# MainControllerPower.net
KiCad netlist of a schematic drawn in Altium Designer
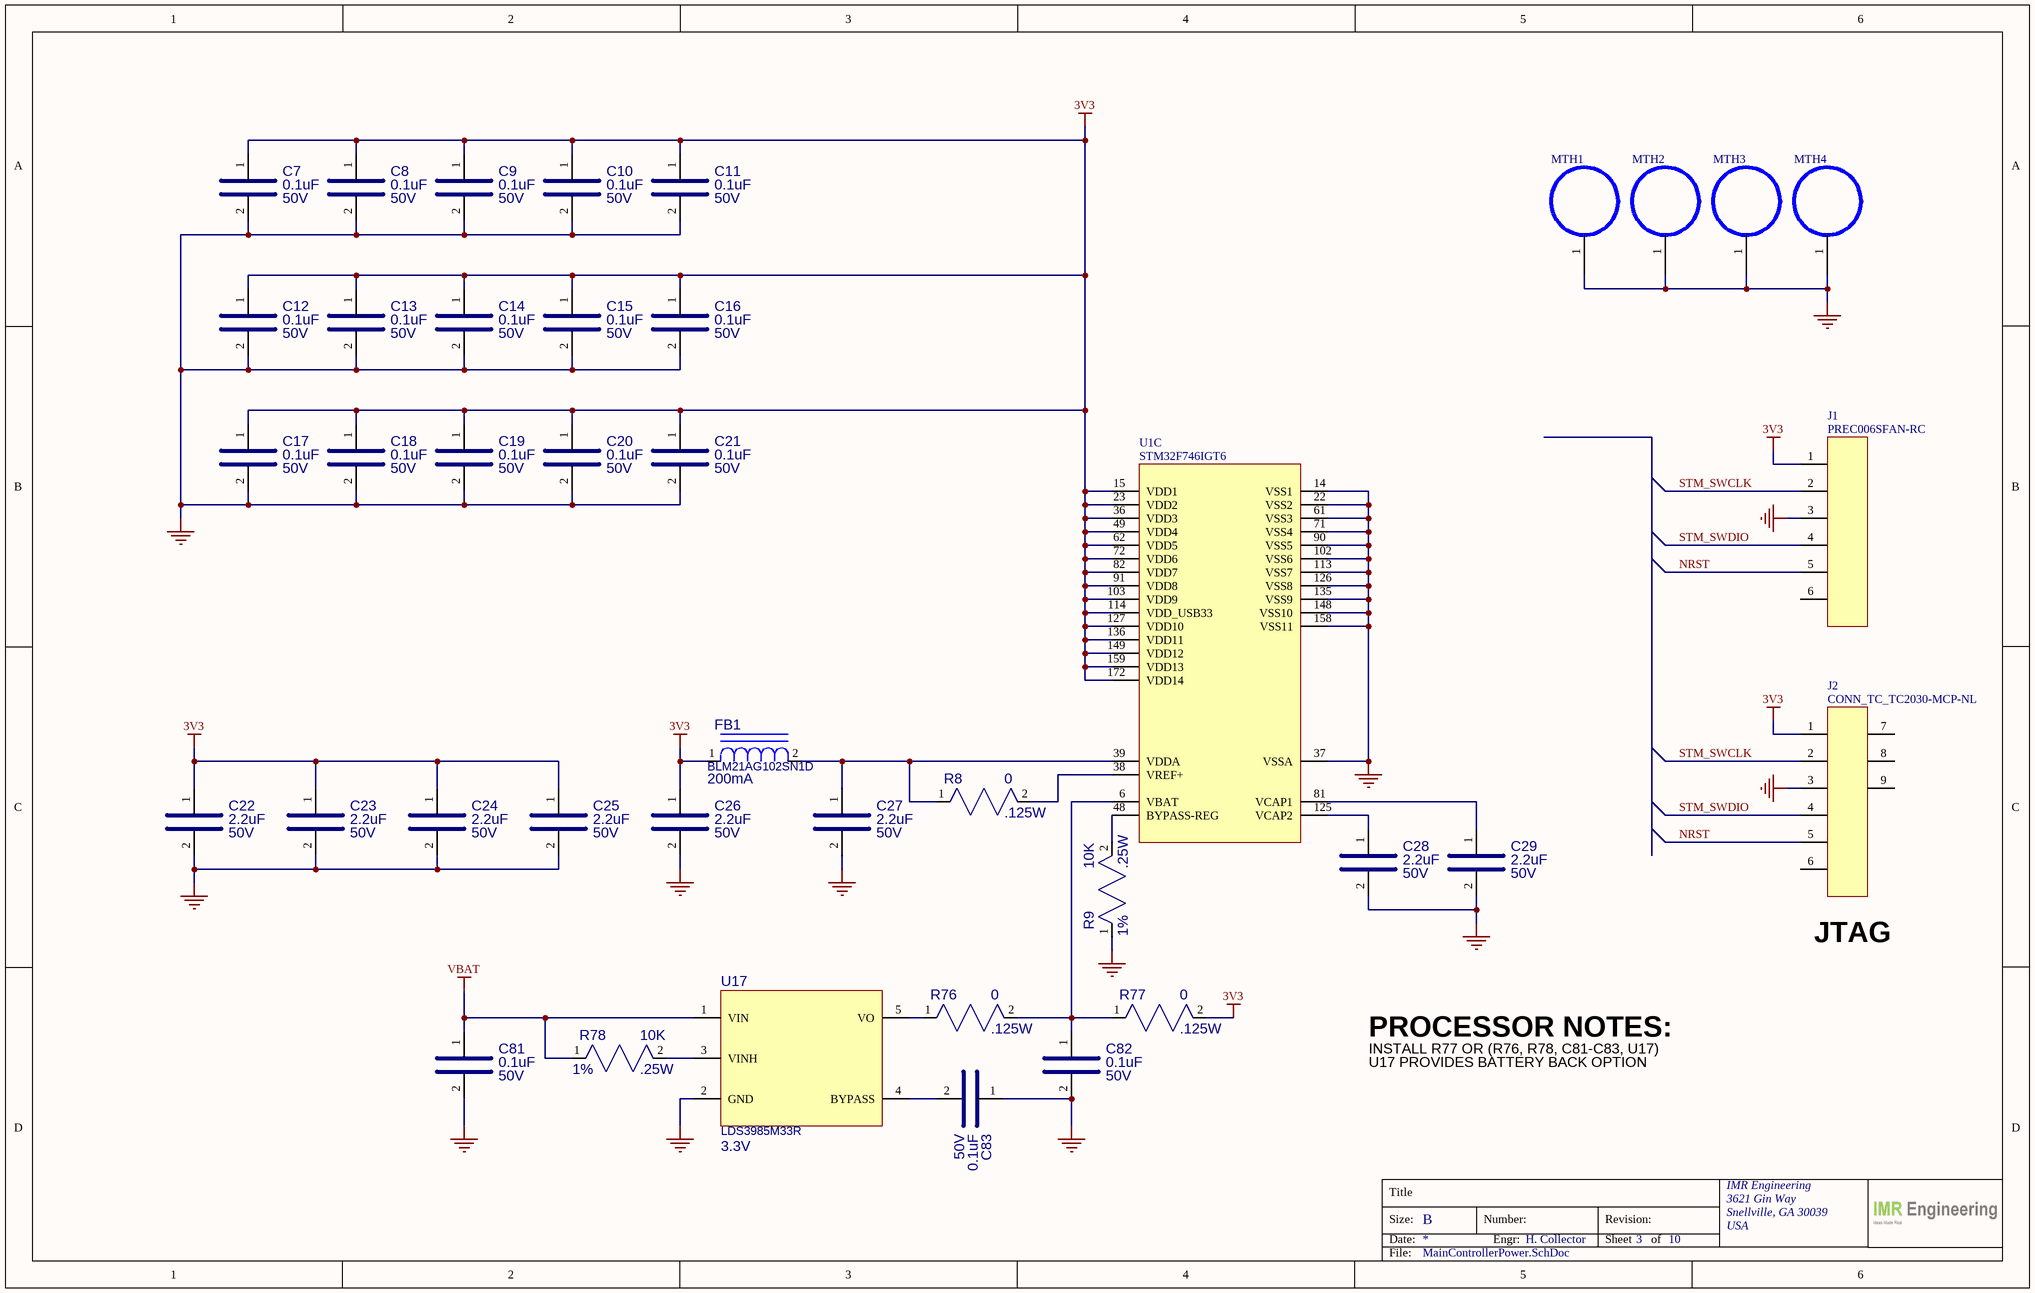
[diagram p0: MainControllerPower.SchDoc]

(export (version "E")
  (design (tool "Eeschema 10.0.6"))
  (components
    (comp (ref "C7")
      (value "0.1uF")
      (footprint "CAP_0603")
      (description "CAP CER 0.1UF 50V X7R 0603")
      (fields (field (name "MFG") "Yageo") (field (name "TOLERANCE") "10%") (field (name "VOLTAGE") "50V"))
      (libsource (lib "IMR_Lib") (part "CAP_0.1UF_50V_0603"))
    )
    (comp (ref "C8")
      (value "0.1uF")
      (footprint "CAP_0603")
      (description "CAP CER 0.1UF 50V X7R 0603")
      (fields (field (name "MFG") "Yageo") (field (name "TOLERANCE") "10%") (field (name "VOLTAGE") "50V"))
      (libsource (lib "IMR_Lib") (part "CAP_0.1UF_50V_0603"))
    )
    (comp (ref "C9")
      (value "0.1uF")
      (footprint "CAP_0603")
      (description "CAP CER 0.1UF 50V X7R 0603")
      (fields (field (name "MFG") "Yageo") (field (name "TOLERANCE") "10%") (field (name "VOLTAGE") "50V"))
      (libsource (lib "IMR_Lib") (part "CAP_0.1UF_50V_0603"))
    )
    (comp (ref "C10")
      (value "0.1uF")
      (footprint "CAP_0603")
      (description "CAP CER 0.1UF 50V X7R 0603")
      (fields (field (name "MFG") "Yageo") (field (name "TOLERANCE") "10%") (field (name "VOLTAGE") "50V"))
      (libsource (lib "IMR_Lib") (part "CAP_0.1UF_50V_0603"))
    )
    (comp (ref "C11")
      (value "0.1uF")
      (footprint "CAP_0603")
      (description "CAP CER 0.1UF 50V X7R 0603")
      (fields (field (name "MFG") "Yageo") (field (name "TOLERANCE") "10%") (field (name "VOLTAGE") "50V"))
      (libsource (lib "IMR_Lib") (part "CAP_0.1UF_50V_0603"))
    )
    (comp (ref "C12")
      (value "0.1uF")
      (footprint "CAP_0603")
      (description "CAP CER 0.1UF 50V X7R 0603")
      (fields (field (name "MFG") "Yageo") (field (name "TOLERANCE") "10%") (field (name "VOLTAGE") "50V"))
      (libsource (lib "IMR_Lib") (part "CAP_0.1UF_50V_0603"))
    )
    (comp (ref "C13")
      (value "0.1uF")
      (footprint "CAP_0603")
      (description "CAP CER 0.1UF 50V X7R 0603")
      (fields (field (name "MFG") "Yageo") (field (name "TOLERANCE") "10%") (field (name "VOLTAGE") "50V"))
      (libsource (lib "IMR_Lib") (part "CAP_0.1UF_50V_0603"))
    )
    (comp (ref "C14")
      (value "0.1uF")
      (footprint "CAP_0603")
      (description "CAP CER 0.1UF 50V X7R 0603")
      (fields (field (name "MFG") "Yageo") (field (name "TOLERANCE") "10%") (field (name "VOLTAGE") "50V"))
      (libsource (lib "IMR_Lib") (part "CAP_0.1UF_50V_0603"))
    )
    (comp (ref "C15")
      (value "0.1uF")
      (footprint "CAP_0603")
      (description "CAP CER 0.1UF 50V X7R 0603")
      (fields (field (name "MFG") "Yageo") (field (name "TOLERANCE") "10%") (field (name "VOLTAGE") "50V"))
      (libsource (lib "IMR_Lib") (part "CAP_0.1UF_50V_0603"))
    )
    (comp (ref "C16")
      (value "0.1uF")
      (footprint "CAP_0603")
      (description "CAP CER 0.1UF 50V X7R 0603")
      (fields (field (name "MFG") "Yageo") (field (name "TOLERANCE") "10%") (field (name "VOLTAGE") "50V"))
      (libsource (lib "IMR_Lib") (part "CAP_0.1UF_50V_0603"))
    )
    (comp (ref "C17")
      (value "0.1uF")
      (footprint "CAP_0603")
      (description "CAP CER 0.1UF 50V X7R 0603")
      (fields (field (name "MFG") "Yageo") (field (name "TOLERANCE") "10%") (field (name "VOLTAGE") "50V"))
      (libsource (lib "IMR_Lib") (part "CAP_0.1UF_50V_0603"))
    )
    (comp (ref "C18")
      (value "0.1uF")
      (footprint "CAP_0603")
      (description "CAP CER 0.1UF 50V X7R 0603")
      (fields (field (name "MFG") "Yageo") (field (name "TOLERANCE") "10%") (field (name "VOLTAGE") "50V"))
      (libsource (lib "IMR_Lib") (part "CAP_0.1UF_50V_0603"))
    )
    (comp (ref "C19")
      (value "0.1uF")
      (footprint "CAP_0603")
      (description "CAP CER 0.1UF 50V X7R 0603")
      (fields (field (name "MFG") "Yageo") (field (name "TOLERANCE") "10%") (field (name "VOLTAGE") "50V"))
      (libsource (lib "IMR_Lib") (part "CAP_0.1UF_50V_0603"))
    )
    (comp (ref "C20")
      (value "0.1uF")
      (footprint "CAP_0603")
      (description "CAP CER 0.1UF 50V X7R 0603")
      (fields (field (name "MFG") "Yageo") (field (name "TOLERANCE") "10%") (field (name "VOLTAGE") "50V"))
      (libsource (lib "IMR_Lib") (part "CAP_0.1UF_50V_0603"))
    )
    (comp (ref "C21")
      (value "0.1uF")
      (footprint "CAP_0603")
      (description "CAP CER 0.1UF 50V X7R 0603")
      (fields (field (name "MFG") "Yageo") (field (name "TOLERANCE") "10%") (field (name "VOLTAGE") "50V"))
      (libsource (lib "IMR_Lib") (part "CAP_0.1UF_50V_0603"))
    )
    (comp (ref "C22")
      (value "2.2uF")
      (footprint "CAP_0805")
      (description "CAP CER 2.2UF 50V X7R 0805")
      (fields
        (field (name "MFG") "Taiyo Yuden")
        (field (name "TOLERANCE") "20%")
        (field (name "VOLTAGE") "50V")
      )
      (libsource (lib "IMR_Lib") (part "CAP_2.2UF_50V_0805"))
    )
    (comp (ref "C23")
      (value "2.2uF")
      (footprint "CAP_0805")
      (description "CAP CER 2.2UF 50V X7R 0805")
      (fields
        (field (name "MFG") "Taiyo Yuden")
        (field (name "TOLERANCE") "20%")
        (field (name "VOLTAGE") "50V")
      )
      (libsource (lib "IMR_Lib") (part "CAP_2.2UF_50V_0805"))
    )
    (comp (ref "C24")
      (value "2.2uF")
      (footprint "CAP_0805")
      (description "CAP CER 2.2UF 50V X7R 0805")
      (fields
        (field (name "MFG") "Taiyo Yuden")
        (field (name "TOLERANCE") "20%")
        (field (name "VOLTAGE") "50V")
      )
      (libsource (lib "IMR_Lib") (part "CAP_2.2UF_50V_0805"))
    )
    (comp (ref "C25")
      (value "2.2uF")
      (footprint "CAP_0805")
      (description "CAP CER 2.2UF 50V X7R 0805")
      (fields
        (field (name "MFG") "Taiyo Yuden")
        (field (name "TOLERANCE") "20%")
        (field (name "VOLTAGE") "50V")
      )
      (libsource (lib "IMR_Lib") (part "CAP_2.2UF_50V_0805"))
    )
    (comp (ref "C26")
      (value "2.2uF")
      (footprint "CAP_0805")
      (description "CAP CER 2.2UF 50V X7R 0805")
      (fields
        (field (name "MFG") "Taiyo Yuden")
        (field (name "TOLERANCE") "20%")
        (field (name "VOLTAGE") "50V")
      )
      (libsource (lib "IMR_Lib") (part "CAP_2.2UF_50V_0805"))
    )
    (comp (ref "C27")
      (value "2.2uF")
      (footprint "CAP_0805")
      (description "CAP CER 2.2UF 50V X7R 0805")
      (fields
        (field (name "MFG") "Taiyo Yuden")
        (field (name "TOLERANCE") "20%")
        (field (name "VOLTAGE") "50V")
      )
      (libsource (lib "IMR_Lib") (part "CAP_2.2UF_50V_0805"))
    )
    (comp (ref "C28")
      (value "2.2uF")
      (footprint "CAP_0805")
      (description "CAP CER 2.2UF 50V X7R 0805")
      (fields
        (field (name "MFG") "Taiyo Yuden")
        (field (name "TOLERANCE") "20%")
        (field (name "VOLTAGE") "50V")
      )
      (libsource (lib "IMR_Lib") (part "CAP_2.2UF_50V_0805"))
    )
    (comp (ref "C29")
      (value "2.2uF")
      (footprint "CAP_0805")
      (description "CAP CER 2.2UF 50V X7R 0805")
      (fields
        (field (name "MFG") "Taiyo Yuden")
        (field (name "TOLERANCE") "20%")
        (field (name "VOLTAGE") "50V")
      )
      (libsource (lib "IMR_Lib") (part "CAP_2.2UF_50V_0805"))
    )
    (comp (ref "C81")
      (value "0.1uF")
      (footprint "CAP_0805")
      (description "CAP CER 0.1UF 50V X7R 0805")
      (fields (field (name "MFG") "AVX") (field (name "TOLERANCE") "10%") (field (name "VOLTAGE") "50V"))
      (libsource (lib "IMR_Lib") (part "CAP_0.1UF_50V_0805"))
    )
    (comp (ref "C82")
      (value "0.1uF")
      (footprint "CAP_0805")
      (description "CAP CER 0.1UF 50V X7R 0805")
      (fields (field (name "MFG") "AVX") (field (name "TOLERANCE") "10%") (field (name "VOLTAGE") "50V"))
      (libsource (lib "IMR_Lib") (part "CAP_0.1UF_50V_0805"))
    )
    (comp (ref "C83")
      (value "0.1uF")
      (footprint "CAP_0805")
      (description "CAP CER 0.1UF 50V X7R 0805")
      (fields (field (name "MFG") "AVX") (field (name "TOLERANCE") "10%") (field (name "VOLTAGE") "50V"))
      (libsource (lib "IMR_Lib") (part "CAP_0.1UF_50V_0805"))
    )
    (comp (ref "FB1")
      (value "200mA")
      (footprint "RES_0805")
      (description "FERRITE, 1KOHM AT 100MHZ, 220MA, .450DCR")
      (fields
        (field (name "MFG") "MURATA")
        (field (name "TOLERANCE") "10%")
        (field (name "MFG_PN") "BLM21AG102SN1D")
      )
      (libsource (lib "IMR_Lib") (part "FERRITE_BLM21AG102SN1D"))
    )
    (comp (ref "J1")
      (value "PREC006SFAN-RC")
      (footprint "HDR_1X6_100MILL")
      (description "CONN HEADER VERT 6POS 2.54MM")
      (fields (field (name "MFG") "Sullins Connector Solutions"))
      (libsource (lib "IMR_Lib") (part "CONN_6P_SINGLE_ROW"))
    )
    (comp (ref "J2")
      (value "CONN_TC_TC2030-MCP-NL")
      (footprint "TC2030-MCP-NL-")
      (description "CABLE TAG-CONNECT IN-CIRCUIT")
      (fields (field (name "MFG") "Tag-Connect LLC"))
      (libsource (lib "IMR_Lib") (part "CONN_TC_TC2030-MCP-NL"))
    )
    (comp (ref "MTH1")
      (value "MOUNT_HOLE_3MM_ID")
      (footprint "MT_HOLE_3MM_5MM")
      (description "3MM IN D. MT HOLE")
      (libsource (lib "IMR_Lib") (part "MOUNT_HOLE_3MM_ID"))
    )
    (comp (ref "MTH2")
      (value "MOUNT_HOLE_3MM_ID")
      (footprint "MT_HOLE_3MM_5MM")
      (description "3MM IN D. MT HOLE")
      (libsource (lib "IMR_Lib") (part "MOUNT_HOLE_3MM_ID"))
    )
    (comp (ref "MTH3")
      (value "MOUNT_HOLE_3MM_ID")
      (footprint "MT_HOLE_3MM_5MM")
      (description "3MM IN D. MT HOLE")
      (libsource (lib "IMR_Lib") (part "MOUNT_HOLE_3MM_ID"))
    )
    (comp (ref "MTH4")
      (value "MOUNT_HOLE_3MM_ID")
      (footprint "MT_HOLE_3MM_5MM")
      (description "3MM IN D. MT HOLE")
      (libsource (lib "IMR_Lib") (part "MOUNT_HOLE_3MM_ID"))
    )
    (comp (ref "R8")
      (value "0")
      (footprint "PMG_RES_0805")
      (description "RES SMD 0 OHM JUMPER 1/8W 0805")
      (fields (field (name "MFG") "Yageo") (field (name "TOLERANCE") "JUMPER") (field (name "POWER") ".125W"))
      (libsource (lib "IMR_Lib") (part "RES_0_0805_1/8W"))
    )
    (comp (ref "R9")
      (value "10K")
      (footprint "RES_0805")
      (description "RES SMD 10K OHM 1% 1/4W 0805")
      (fields
        (field (name "MFG") "KOA Speer Electronics, Inc.")
        (field (name "TOLERANCE") "1%")
        (field (name "POWER") ".25W")
        (field (name "Comment") "SG73S2ATTD1002F")
      )
      (libsource (lib "IMR_Lib") (part "RES_10K_0805_1/4W_1%"))
    )
    (comp (ref "R76")
      (value "0")
      (footprint "PMG_RES_0805")
      (description "RES SMD 0 OHM JUMPER 1/8W 0805")
      (fields (field (name "MFG") "Yageo") (field (name "TOLERANCE") "JUMPER") (field (name "POWER") ".125W"))
      (libsource (lib "IMR_Lib") (part "RES_0_0805_1/8W"))
    )
    (comp (ref "R77")
      (value "0")
      (footprint "PMG_RES_0805")
      (description "RES SMD 0 OHM JUMPER 1/8W 0805")
      (fields (field (name "MFG") "Yageo") (field (name "TOLERANCE") "JUMPER") (field (name "POWER") ".125W"))
      (libsource (lib "IMR_Lib") (part "RES_0_0805_1/8W"))
    )
    (comp (ref "R78")
      (value "10K")
      (footprint "RES_0805")
      (description "RES SMD 10K OHM 1% 1/4W 0805")
      (fields
        (field (name "MFG") "KOA Speer Electronics, Inc.")
        (field (name "TOLERANCE") "1%")
        (field (name "POWER") ".25W")
        (field (name "Comment") "SG73S2ATTD1002F")
      )
      (libsource (lib "IMR_Lib") (part "RES_10K_0805_1/4W_1%"))
    )
    (comp (ref "U1")
      (value "STM32F746IGT6")
      (footprint "QFP50P2600X2600X160-176N")
      (description "STM32F746NGH6 (STM32F7 Birdie) TBGA216")
      (fields (field (name "MFG") "STMicroelectronics"))
      (libsource (lib "IMR_Lib") (part "IC_STM32F746NGH6U"))
    )
    (comp (ref "U17")
      (value "3.3V")
      (footprint "SOT23-5")
      (description "IC REG LINEAR 3.3V 300MA SOT23-5")
      (fields
        (field (name "MFG") "STMicroelectronics")
        (field (name "MFG_PN") "LDS3985M33R")
        (field (name "Comment") "LDS3985M33R")
      )
      (libsource (lib "IMR_Lib") (part "IC_LDS3985M33R"))
    )
  )
  (nets
    (net (code "1") (name "/NRST") (class "Default")
      (node (ref "J1") (pin "5") (pintype "passive"))
      (node (ref "J2") (pin "5") (pintype "passive"))
    )
    (net (code "2") (name "/STM_SWCLK") (class "Default")
      (node (ref "J1") (pin "2") (pintype "passive"))
      (node (ref "J2") (pin "2") (pintype "passive"))
    )
    (net (code "3") (name "/STM_SWDIO") (class "Default")
      (node (ref "J1") (pin "4") (pintype "passive"))
      (node (ref "J2") (pin "4") (pintype "passive"))
    )
    (net (code "4") (name "3V3") (class "Default")
      (node (ref "C10") (pin "1") (pinfunction "1_1") (pintype "passive"))
      (node (ref "C11") (pin "1") (pinfunction "1_1") (pintype "passive"))
      (node (ref "C12") (pin "1") (pinfunction "1_1") (pintype "passive"))
      (node (ref "C13") (pin "1") (pinfunction "1_1") (pintype "passive"))
      (node (ref "C14") (pin "1") (pinfunction "1_1") (pintype "passive"))
      (node (ref "C15") (pin "1") (pinfunction "1_1") (pintype "passive"))
      (node (ref "C16") (pin "1") (pinfunction "1_1") (pintype "passive"))
      (node (ref "C17") (pin "1") (pinfunction "1_1") (pintype "passive"))
      (node (ref "C18") (pin "1") (pinfunction "1_1") (pintype "passive"))
      (node (ref "C19") (pin "1") (pinfunction "1_1") (pintype "passive"))
      (node (ref "C20") (pin "1") (pinfunction "1_1") (pintype "passive"))
      (node (ref "C21") (pin "1") (pinfunction "1_1") (pintype "passive"))
      (node (ref "C22") (pin "1") (pinfunction "1_1") (pintype "passive"))
      (node (ref "C23") (pin "1") (pinfunction "1_1") (pintype "passive"))
      (node (ref "C24") (pin "1") (pinfunction "1_1") (pintype "passive"))
      (node (ref "C25") (pin "1") (pinfunction "1_1") (pintype "passive"))
      (node (ref "C26") (pin "1") (pinfunction "1_1") (pintype "passive"))
      (node (ref "C7") (pin "1") (pinfunction "1_1") (pintype "passive"))
      (node (ref "C8") (pin "1") (pinfunction "1_1") (pintype "passive"))
      (node (ref "C9") (pin "1") (pinfunction "1_1") (pintype "passive"))
      (node (ref "FB1") (pin "1") (pinfunction "1_1") (pintype "passive"))
      (node (ref "J1") (pin "1") (pinfunction "1_1") (pintype "passive"))
      (node (ref "J2") (pin "1") (pinfunction "1_1") (pintype "passive"))
      (node (ref "R77") (pin "2") (pinfunction "2_2") (pintype "passive"))
      (node (ref "U1") (pin "103") (pinfunction "VDD9_103") (pintype "passive"))
      (node (ref "U1") (pin "114") (pinfunction "VDD_USB33_114") (pintype "passive"))
      (node (ref "U1") (pin "127") (pinfunction "VDD10_127") (pintype "passive"))
      (node (ref "U1") (pin "136") (pinfunction "VDD11_136") (pintype "passive"))
      (node (ref "U1") (pin "149") (pinfunction "VDD12_149") (pintype "passive"))
      (node (ref "U1") (pin "15") (pinfunction "VDD1_15") (pintype "passive"))
      (node (ref "U1") (pin "159") (pinfunction "VDD13_159") (pintype "passive"))
      (node (ref "U1") (pin "172") (pinfunction "VDD14_172") (pintype "passive"))
      (node (ref "U1") (pin "23") (pinfunction "VDD2_23") (pintype "passive"))
      (node (ref "U1") (pin "36") (pinfunction "VDD3_36") (pintype "passive"))
      (node (ref "U1") (pin "49") (pinfunction "VDD4_49") (pintype "passive"))
      (node (ref "U1") (pin "62") (pinfunction "VDD5_62") (pintype "passive"))
      (node (ref "U1") (pin "72") (pinfunction "VDD6_72") (pintype "passive"))
      (node (ref "U1") (pin "82") (pinfunction "VDD7_82") (pintype "passive"))
      (node (ref "U1") (pin "91") (pinfunction "VDD8_91") (pintype "passive"))
    )
    (net (code "5") (name "GND") (class "Default")
      (node (ref "C10") (pin "2") (pinfunction "2_2") (pintype "passive"))
      (node (ref "C11") (pin "2") (pinfunction "2_2") (pintype "passive"))
      (node (ref "C12") (pin "2") (pinfunction "2_2") (pintype "passive"))
      (node (ref "C13") (pin "2") (pinfunction "2_2") (pintype "passive"))
      (node (ref "C14") (pin "2") (pinfunction "2_2") (pintype "passive"))
      (node (ref "C15") (pin "2") (pinfunction "2_2") (pintype "passive"))
      (node (ref "C16") (pin "2") (pinfunction "2_2") (pintype "passive"))
      (node (ref "C17") (pin "2") (pinfunction "2_2") (pintype "passive"))
      (node (ref "C18") (pin "2") (pinfunction "2_2") (pintype "passive"))
      (node (ref "C19") (pin "2") (pinfunction "2_2") (pintype "passive"))
      (node (ref "C20") (pin "2") (pinfunction "2_2") (pintype "passive"))
      (node (ref "C21") (pin "2") (pinfunction "2_2") (pintype "passive"))
      (node (ref "C22") (pin "2") (pinfunction "2_2") (pintype "passive"))
      (node (ref "C23") (pin "2") (pinfunction "2_2") (pintype "passive"))
      (node (ref "C24") (pin "2") (pinfunction "2_2") (pintype "passive"))
      (node (ref "C25") (pin "2") (pinfunction "2_2") (pintype "passive"))
      (node (ref "C26") (pin "2") (pinfunction "2_2") (pintype "passive"))
      (node (ref "C27") (pin "2") (pinfunction "2_2") (pintype "passive"))
      (node (ref "C28") (pin "2") (pinfunction "2_2") (pintype "passive"))
      (node (ref "C29") (pin "2") (pinfunction "2_2") (pintype "passive"))
      (node (ref "C7") (pin "2") (pinfunction "2_2") (pintype "passive"))
      (node (ref "C8") (pin "2") (pinfunction "2_2") (pintype "passive"))
      (node (ref "C81") (pin "2") (pinfunction "2_2") (pintype "passive"))
      (node (ref "C82") (pin "2") (pinfunction "2_2") (pintype "passive"))
      (node (ref "C83") (pin "1") (pinfunction "1_1") (pintype "passive"))
      (node (ref "C9") (pin "2") (pinfunction "2_2") (pintype "passive"))
      (node (ref "J1") (pin "3") (pintype "passive"))
      (node (ref "J2") (pin "3") (pintype "passive"))
      (node (ref "MTH1") (pin "1") (pinfunction "1_1") (pintype "passive"))
      (node (ref "MTH2") (pin "1") (pinfunction "1_1") (pintype "passive"))
      (node (ref "MTH3") (pin "1") (pinfunction "1_1") (pintype "passive"))
      (node (ref "MTH4") (pin "1") (pinfunction "1_1") (pintype "passive"))
      (node (ref "R9") (pin "1") (pinfunction "1_1") (pintype "passive"))
      (node (ref "U1") (pin "102") (pinfunction "VSS6_102") (pintype "passive"))
      (node (ref "U1") (pin "113") (pinfunction "VSS7_113") (pintype "passive"))
      (node (ref "U1") (pin "126") (pinfunction "VSS8_126") (pintype "passive"))
      (node (ref "U1") (pin "135") (pinfunction "VSS9_135") (pintype "passive"))
      (node (ref "U1") (pin "14") (pinfunction "VSS1_14") (pintype "passive"))
      (node (ref "U1") (pin "148") (pinfunction "VSS10_148") (pintype "passive"))
      (node (ref "U1") (pin "158") (pinfunction "VSS11_158") (pintype "passive"))
      (node (ref "U1") (pin "22") (pinfunction "VSS2_22") (pintype "passive"))
      (node (ref "U1") (pin "37") (pinfunction "VSSA_37") (pintype "passive"))
      (node (ref "U1") (pin "61") (pinfunction "VSS3_61") (pintype "passive"))
      (node (ref "U1") (pin "71") (pinfunction "VSS4_71") (pintype "passive"))
      (node (ref "U1") (pin "90") (pinfunction "VSS5_90") (pintype "passive"))
      (node (ref "U17") (pin "2") (pinfunction "GND_2") (pintype "passive"))
    )
    (net (code "6") (name "Net-(U1C-BYPASS-REG)") (class "Default")
      (node (ref "R9") (pin "2") (pinfunction "2_2") (pintype "passive"))
      (node (ref "U1") (pin "48") (pinfunction "BYPASS-REG_48") (pintype "passive"))
    )
    (net (code "7") (name "Net-(U1C-VBAT)") (class "Default")
      (node (ref "C82") (pin "1") (pinfunction "1_1") (pintype "passive"))
      (node (ref "R76") (pin "2") (pinfunction "2_2") (pintype "passive"))
      (node (ref "R77") (pin "1") (pinfunction "1_1") (pintype "passive"))
      (node (ref "U1") (pin "6") (pinfunction "VBAT_6") (pintype "passive"))
    )
    (net (code "8") (name "Net-(U1C-VCAP1)") (class "Default")
      (node (ref "C29") (pin "1") (pinfunction "1_1") (pintype "passive"))
      (node (ref "U1") (pin "81") (pinfunction "VCAP1_81") (pintype "passive"))
    )
    (net (code "9") (name "Net-(U1C-VCAP2)") (class "Default")
      (node (ref "C28") (pin "1") (pinfunction "1_1") (pintype "passive"))
      (node (ref "U1") (pin "125") (pinfunction "VCAP2_125") (pintype "passive"))
    )
    (net (code "10") (name "Net-(U1C-VDDA)") (class "Default")
      (node (ref "C27") (pin "1") (pinfunction "1_1") (pintype "passive"))
      (node (ref "FB1") (pin "2") (pinfunction "2_2") (pintype "passive"))
      (node (ref "R8") (pin "1") (pinfunction "1_1") (pintype "passive"))
      (node (ref "U1") (pin "39") (pinfunction "VDDA_39") (pintype "passive"))
    )
    (net (code "11") (name "Net-(U1C-VREF+)") (class "Default")
      (node (ref "R8") (pin "2") (pinfunction "2_2") (pintype "passive"))
      (node (ref "U1") (pin "38") (pinfunction "VREF+_38") (pintype "passive"))
    )
    (net (code "12") (name "Net-(U17-BYPASS)") (class "Default")
      (node (ref "C83") (pin "2") (pinfunction "2_2") (pintype "passive"))
      (node (ref "U17") (pin "4") (pinfunction "BYPASS_4") (pintype "passive"))
    )
    (net (code "13") (name "Net-(U17-VINH)") (class "Default")
      (node (ref "R78") (pin "2") (pinfunction "2_2") (pintype "passive"))
      (node (ref "U17") (pin "3") (pinfunction "VINH_3") (pintype "passive"))
    )
    (net (code "14") (name "Net-(U17-VO)") (class "Default")
      (node (ref "R76") (pin "1") (pinfunction "1_1") (pintype "passive"))
      (node (ref "U17") (pin "5") (pinfunction "VO_5") (pintype "passive"))
    )
    (net (code "15") (name "VBAT") (class "Default")
      (node (ref "C81") (pin "1") (pinfunction "1_1") (pintype "passive"))
      (node (ref "R78") (pin "1") (pinfunction "1_1") (pintype "passive"))
      (node (ref "U17") (pin "1") (pinfunction "VIN_1") (pintype "passive"))
    )
    (net (code "16") (name "unconnected-(J1-Pad6)") (class "Default")
      (node (ref "J1") (pin "6") (pintype "passive"))
    )
    (net (code "17") (name "unconnected-(J2-Pad6)") (class "Default")
      (node (ref "J2") (pin "6") (pintype "passive"))
    )
    (net (code "18") (name "unconnected-(J2-Pad7)") (class "Default")
      (node (ref "J2") (pin "7") (pinfunction "7_7") (pintype "passive"))
    )
    (net (code "19") (name "unconnected-(J2-Pad8)") (class "Default")
      (node (ref "J2") (pin "8") (pinfunction "8_8") (pintype "passive"))
    )
    (net (code "20") (name "unconnected-(J2-Pad9)") (class "Default")
      (node (ref "J2") (pin "9") (pinfunction "9_9") (pintype "passive"))
    )
  )
)
